# Back.net
KiCad netlist of a schematic drawn in EAGLE
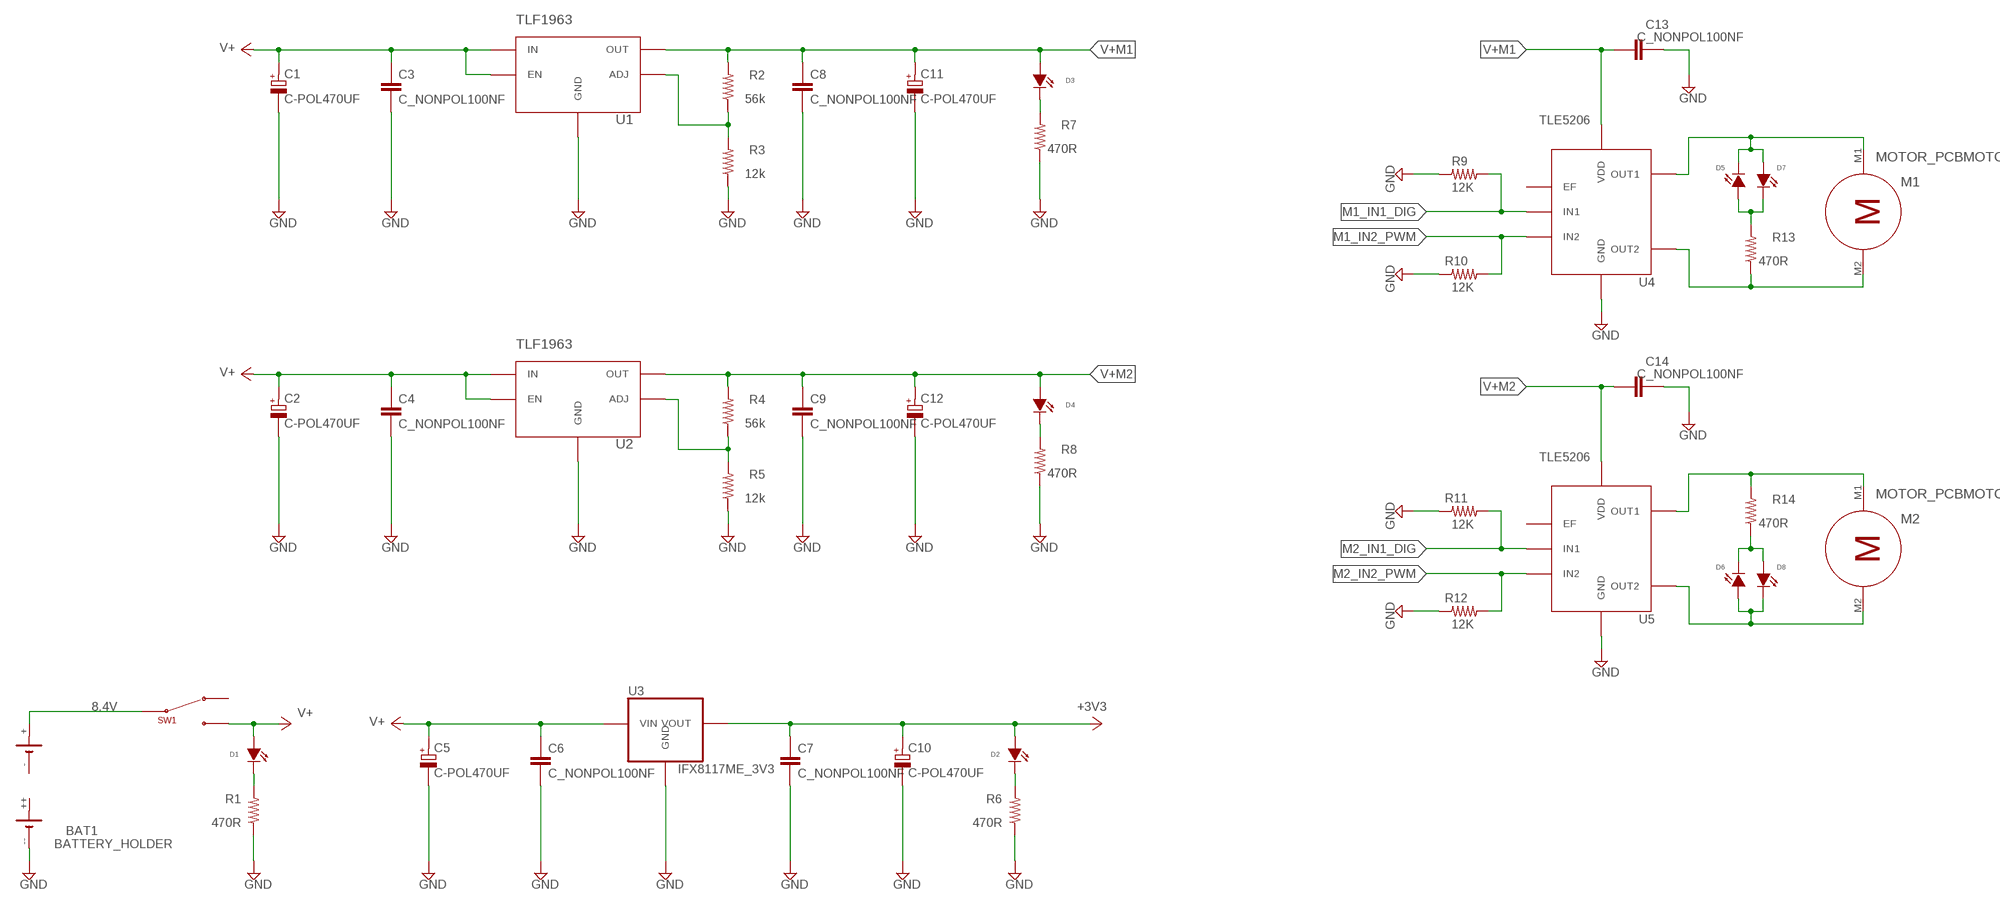
[diagram p0: schematic, sheet 1, part 1 of 2]
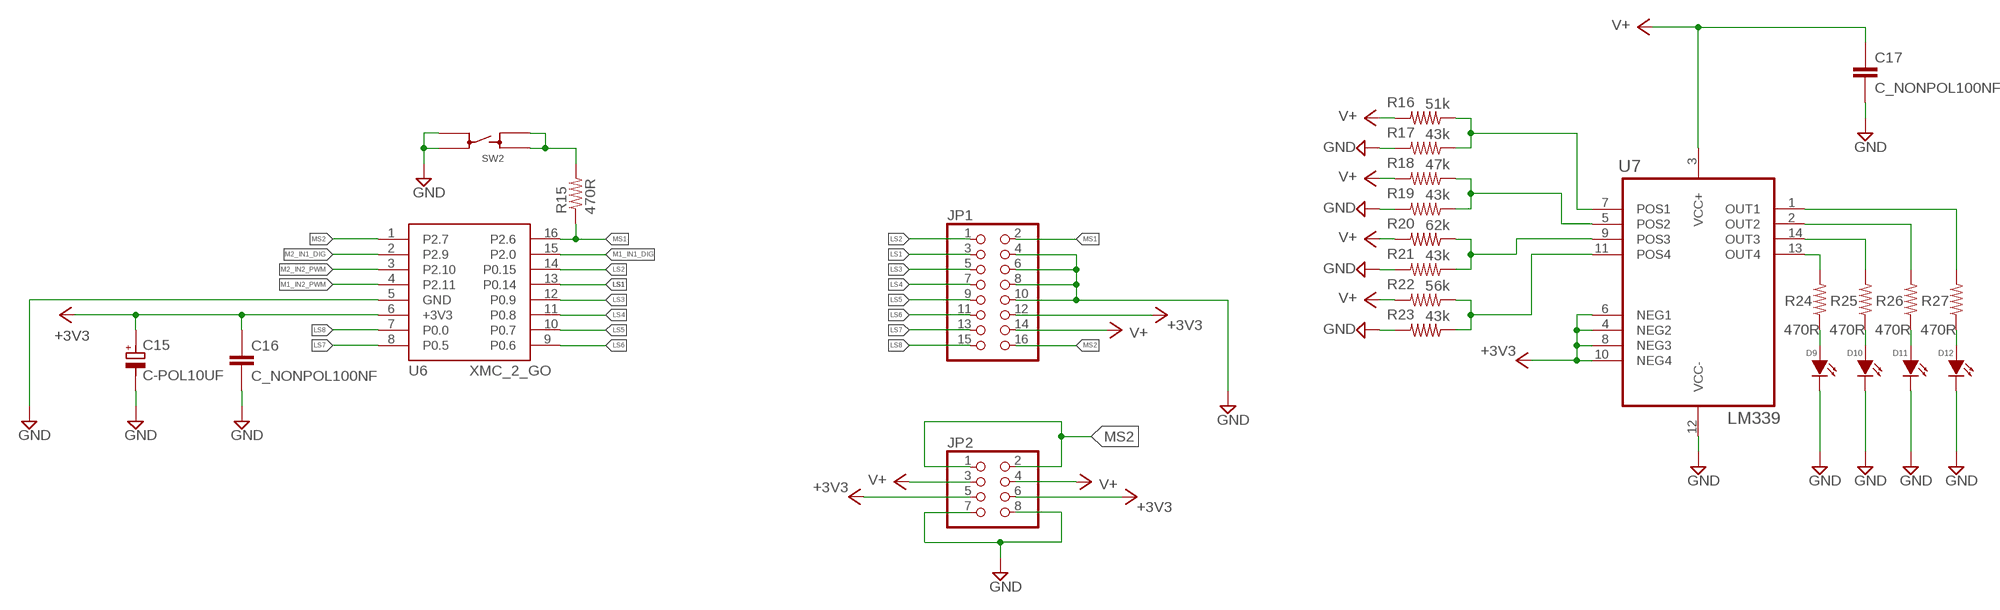
[diagram p1: schematic, sheet 1, part 2 of 2]

(export (version "E")
  (design (tool "Eeschema 10.0.6"))
  (components
    (comp (ref "BAT1")
      (value "BATTERY_HOLDER")
      (footprint "eagle-import:BATT_SUPPORT_KEYSTONE")
      (libsource (lib "eagle-import") (part "BATTERY_HOLDER"))
    )
    (comp (ref "C1")
      (value "C-POL470UF")
      (footprint "eagle-import:E3,5-8")
      (libsource (lib "eagle-import") (part "C-POL470UF"))
    )
    (comp (ref "C2")
      (value "C-POL470UF")
      (footprint "eagle-import:E3,5-8")
      (libsource (lib "eagle-import") (part "C-POL470UF"))
    )
    (comp (ref "C3")
      (value "C_NONPOL100NF")
      (footprint "eagle-import:C1206")
      (libsource (lib "eagle-import") (part "C_NONPOL100NF"))
    )
    (comp (ref "C4")
      (value "C_NONPOL100NF")
      (footprint "eagle-import:C1206")
      (libsource (lib "eagle-import") (part "C_NONPOL100NF"))
    )
    (comp (ref "C5")
      (value "C-POL470UF")
      (footprint "eagle-import:E3,5-8")
      (libsource (lib "eagle-import") (part "C-POL470UF"))
    )
    (comp (ref "C6")
      (value "C_NONPOL100NF")
      (footprint "eagle-import:C1206")
      (libsource (lib "eagle-import") (part "C_NONPOL100NF"))
    )
    (comp (ref "C7")
      (value "C_NONPOL100NF")
      (footprint "eagle-import:C1206")
      (libsource (lib "eagle-import") (part "C_NONPOL100NF"))
    )
    (comp (ref "C8")
      (value "C_NONPOL100NF")
      (footprint "eagle-import:C1206")
      (libsource (lib "eagle-import") (part "C_NONPOL100NF"))
    )
    (comp (ref "C9")
      (value "C_NONPOL100NF")
      (footprint "eagle-import:C1206")
      (libsource (lib "eagle-import") (part "C_NONPOL100NF"))
    )
    (comp (ref "C10")
      (value "C-POL470UF")
      (footprint "eagle-import:E3,5-8")
      (libsource (lib "eagle-import") (part "C-POL470UF"))
    )
    (comp (ref "C11")
      (value "C-POL470UF")
      (footprint "eagle-import:E3,5-8")
      (libsource (lib "eagle-import") (part "C-POL470UF"))
    )
    (comp (ref "C12")
      (value "C-POL470UF")
      (footprint "eagle-import:E3,5-8")
      (libsource (lib "eagle-import") (part "C-POL470UF"))
    )
    (comp (ref "C13")
      (value "C_NONPOL100NF")
      (footprint "eagle-import:C1206")
      (libsource (lib "eagle-import") (part "C_NONPOL100NF"))
    )
    (comp (ref "C14")
      (value "C_NONPOL100NF")
      (footprint "eagle-import:C1206")
      (libsource (lib "eagle-import") (part "C_NONPOL100NF"))
    )
    (comp (ref "C15")
      (value "C-POL10UF")
      (footprint "eagle-import:PANASONIC_B")
      (libsource (lib "eagle-import") (part "C-POL10UF"))
    )
    (comp (ref "C16")
      (value "C_NONPOL100NF")
      (footprint "eagle-import:C1206")
      (libsource (lib "eagle-import") (part "C_NONPOL100NF"))
    )
    (comp (ref "C17")
      (value "C_NONPOL100NF")
      (footprint "eagle-import:C1206")
      (libsource (lib "eagle-import") (part "C_NONPOL100NF"))
    )
    (comp (ref "D1")
      (value "LED")
      (footprint "eagle-import:CHIPLED_1206")
      (libsource (lib "eagle-import") (part "LED"))
    )
    (comp (ref "D2")
      (value "LED")
      (footprint "eagle-import:CHIPLED_1206")
      (libsource (lib "eagle-import") (part "LED"))
    )
    (comp (ref "D3")
      (value "LED")
      (footprint "eagle-import:CHIPLED_1206")
      (libsource (lib "eagle-import") (part "LED"))
    )
    (comp (ref "D4")
      (value "LED")
      (footprint "eagle-import:CHIPLED_1206")
      (libsource (lib "eagle-import") (part "LED"))
    )
    (comp (ref "D5")
      (value "LED")
      (footprint "eagle-import:CHIPLED_1206")
      (libsource (lib "eagle-import") (part "LED"))
    )
    (comp (ref "D6")
      (value "LED")
      (footprint "eagle-import:CHIPLED_1206")
      (libsource (lib "eagle-import") (part "LED"))
    )
    (comp (ref "D7")
      (value "LED")
      (footprint "eagle-import:CHIPLED_1206")
      (libsource (lib "eagle-import") (part "LED"))
    )
    (comp (ref "D8")
      (value "LED")
      (footprint "eagle-import:CHIPLED_1206")
      (libsource (lib "eagle-import") (part "LED"))
    )
    (comp (ref "D9")
      (value "LED")
      (footprint "eagle-import:CHIPLED_1206")
      (libsource (lib "eagle-import") (part "LED"))
    )
    (comp (ref "D10")
      (value "LED")
      (footprint "eagle-import:CHIPLED_1206")
      (libsource (lib "eagle-import") (part "LED"))
    )
    (comp (ref "D11")
      (value "LED")
      (footprint "eagle-import:CHIPLED_1206")
      (libsource (lib "eagle-import") (part "LED"))
    )
    (comp (ref "D12")
      (value "LED")
      (footprint "eagle-import:CHIPLED_1206")
      (libsource (lib "eagle-import") (part "LED"))
    )
    (comp (ref "JP1")
      (value "PINHD-2X8")
      (footprint "eagle-import:2X08")
      (libsource (lib "eagle-import") (part "PINHD-2X8"))
    )
    (comp (ref "JP2")
      (value "PINHD-2X4")
      (footprint "eagle-import:2X04")
      (libsource (lib "eagle-import") (part "PINHD-2X4"))
    )
    (comp (ref "M1")
      (value "MOTOR_PCBMOTOR")
      (footprint "eagle-import:MICRO-MOTOR")
      (libsource (lib "eagle-import") (part "MOTOR_PCBMOTOR"))
    )
    (comp (ref "M2")
      (value "MOTOR_PCBMOTOR")
      (footprint "eagle-import:MICRO-MOTOR")
      (libsource (lib "eagle-import") (part "MOTOR_PCBMOTOR"))
    )
    (comp (ref "R1")
      (value "470R")
      (footprint "eagle-import:R1206")
      (libsource (lib "eagle-import") (part "R1206"))
    )
    (comp (ref "R2")
      (value "56k")
      (footprint "eagle-import:R1206")
      (libsource (lib "eagle-import") (part "R1206"))
    )
    (comp (ref "R3")
      (value "12k")
      (footprint "eagle-import:R1206")
      (libsource (lib "eagle-import") (part "R1206"))
    )
    (comp (ref "R4")
      (value "56k")
      (footprint "eagle-import:R1206")
      (libsource (lib "eagle-import") (part "R1206"))
    )
    (comp (ref "R5")
      (value "12k")
      (footprint "eagle-import:R1206")
      (libsource (lib "eagle-import") (part "R1206"))
    )
    (comp (ref "R6")
      (value "470R")
      (footprint "eagle-import:R1206")
      (libsource (lib "eagle-import") (part "R1206"))
    )
    (comp (ref "R7")
      (value "470R")
      (footprint "eagle-import:R1206")
      (libsource (lib "eagle-import") (part "R1206"))
    )
    (comp (ref "R8")
      (value "470R")
      (footprint "eagle-import:R1206")
      (libsource (lib "eagle-import") (part "R1206"))
    )
    (comp (ref "R9")
      (value "12K")
      (footprint "eagle-import:R1206")
      (libsource (lib "eagle-import") (part "R1206"))
    )
    (comp (ref "R10")
      (value "12K")
      (footprint "eagle-import:R1206")
      (libsource (lib "eagle-import") (part "R1206"))
    )
    (comp (ref "R11")
      (value "12K")
      (footprint "eagle-import:R1206")
      (libsource (lib "eagle-import") (part "R1206"))
    )
    (comp (ref "R12")
      (value "12K")
      (footprint "eagle-import:R1206")
      (libsource (lib "eagle-import") (part "R1206"))
    )
    (comp (ref "R13")
      (value "470R")
      (footprint "eagle-import:R1206")
      (libsource (lib "eagle-import") (part "R1206"))
    )
    (comp (ref "R14")
      (value "470R")
      (footprint "eagle-import:R1206")
      (libsource (lib "eagle-import") (part "R1206"))
    )
    (comp (ref "R15")
      (value "470R")
      (footprint "eagle-import:R1206")
      (libsource (lib "eagle-import") (part "R1206"))
    )
    (comp (ref "R16")
      (value "51k")
      (footprint "eagle-import:R1206")
      (libsource (lib "eagle-import") (part "R1206"))
    )
    (comp (ref "R17")
      (value "43k")
      (footprint "eagle-import:R1206")
      (libsource (lib "eagle-import") (part "R1206"))
    )
    (comp (ref "R18")
      (value "47k")
      (footprint "eagle-import:R1206")
      (libsource (lib "eagle-import") (part "R1206"))
    )
    (comp (ref "R19")
      (value "43k")
      (footprint "eagle-import:R1206")
      (libsource (lib "eagle-import") (part "R1206"))
    )
    (comp (ref "R20")
      (value "62k")
      (footprint "eagle-import:R1206")
      (libsource (lib "eagle-import") (part "R1206"))
    )
    (comp (ref "R21")
      (value "43k")
      (footprint "eagle-import:R1206")
      (libsource (lib "eagle-import") (part "R1206"))
    )
    (comp (ref "R22")
      (value "56k")
      (footprint "eagle-import:R1206")
      (libsource (lib "eagle-import") (part "R1206"))
    )
    (comp (ref "R23")
      (value "43k")
      (footprint "eagle-import:R1206")
      (libsource (lib "eagle-import") (part "R1206"))
    )
    (comp (ref "R24")
      (value "470R")
      (footprint "eagle-import:R1206")
      (libsource (lib "eagle-import") (part "R1206"))
    )
    (comp (ref "R25")
      (value "470R")
      (footprint "eagle-import:R1206")
      (libsource (lib "eagle-import") (part "R1206"))
    )
    (comp (ref "R26")
      (value "470R")
      (footprint "eagle-import:R1206")
      (libsource (lib "eagle-import") (part "R1206"))
    )
    (comp (ref "R27")
      (value "470R")
      (footprint "eagle-import:R1206")
      (libsource (lib "eagle-import") (part "R1206"))
    )
    (comp (ref "SW1")
      (value "SWITCH1OFF2")
      (footprint "eagle-import:MS111")
      (libsource (lib "eagle-import") (part "SWITCH1OFF2"))
    )
    (comp (ref "SW2")
      (value "PUSH_BUTTON_SMD")
      (footprint "eagle-import:SWPB_SMD")
      (libsource (lib "eagle-import") (part "PUSH_BUTTON_SMD"))
    )
    (comp (ref "U1")
      (value "TLF1963")
      (footprint "eagle-import:INF-PG-TO252-5-11_L_1PRIMARY")
      (libsource (lib "eagle-import") (part "TLF1963"))
    )
    (comp (ref "U2")
      (value "TLF1963")
      (footprint "eagle-import:INF-PG-TO252-5-11_L_1PRIMARY")
      (libsource (lib "eagle-import") (part "TLF1963"))
    )
    (comp (ref "U3")
      (value "IFX8117ME_3V3")
      (footprint "eagle-import:INF-PG-SOT223_SC-73_M_1PRIMARY")
      (libsource (lib "eagle-import") (part "IFX8117ME_3V3"))
    )
    (comp (ref "U4")
      (value "TLE5206")
      (footprint "eagle-import:INF-PG-TO263-7-1_L_1PRIMARY")
      (libsource (lib "eagle-import") (part "TLE5206"))
    )
    (comp (ref "U5")
      (value "TLE5206")
      (footprint "eagle-import:INF-PG-TO263-7-1_L_1PRIMARY")
      (libsource (lib "eagle-import") (part "TLE5206"))
    )
    (comp (ref "U6")
      (value "XMC_2_GO")
      (footprint "eagle-import:XMC_2_GO")
      (libsource (lib "eagle-import") (part "XMC_2_GO"))
    )
    (comp (ref "U7")
      (value "LM339")
      (footprint "eagle-import:SO14")
      (libsource (lib "eagle-import") (part "LM339"))
    )
  )
  (nets
    (net (code "1") (name "+3V3") (class "Default")
      (node (ref "C10") (pin "+") (pinfunction "+_+") (pintype "passive"))
      (node (ref "C15") (pin "+") (pinfunction "+_+") (pintype "passive"))
      (node (ref "C16") (pin "1") (pinfunction "1_1") (pintype "passive"))
      (node (ref "C7") (pin "1") (pinfunction "1_1") (pintype "passive"))
      (node (ref "D2") (pin "A") (pinfunction "A_A") (pintype "bidirectional"))
      (node (ref "JP1") (pin "12") (pinfunction "12_12") (pintype "passive"))
      (node (ref "JP2") (pin "5") (pinfunction "5_5") (pintype "passive"))
      (node (ref "JP2") (pin "6") (pinfunction "6_6") (pintype "passive"))
      (node (ref "U3") (pin "2") (pinfunction "VOUT_2") (pintype "power_in"))
      (node (ref "U3") (pin "4") (pinfunction "VOUT_4") (pintype "power_in"))
      (node (ref "U6") (pin "6") (pinfunction "+3V3_6") (pintype "bidirectional"))
      (node (ref "U7") (pin "10") (pinfunction "NEG4_10") (pintype "input"))
      (node (ref "U7") (pin "4") (pinfunction "NEG2_4") (pintype "input"))
      (node (ref "U7") (pin "6") (pinfunction "NEG1_6") (pintype "input"))
      (node (ref "U7") (pin "8") (pinfunction "NEG3_8") (pintype "input"))
    )
    (net (code "2") (name "/8.4V") (class "Default")
      (node (ref "BAT1") (pin "+") (pinfunction "+_+") (pintype "passive"))
      (node (ref "SW1") (pin "P$2") (pinfunction "COM_P$2") (pintype "bidirectional"))
    )
    (net (code "3") (name "GND") (class "Default")
      (node (ref "BAT1") (pin "--") (pinfunction "-1_--") (pintype "passive"))
      (node (ref "C1") (pin "-") (pinfunction "-_-") (pintype "passive"))
      (node (ref "C10") (pin "-") (pinfunction "-_-") (pintype "passive"))
      (node (ref "C11") (pin "-") (pinfunction "-_-") (pintype "passive"))
      (node (ref "C12") (pin "-") (pinfunction "-_-") (pintype "passive"))
      (node (ref "C13") (pin "2") (pinfunction "2_2") (pintype "passive"))
      (node (ref "C14") (pin "2") (pinfunction "2_2") (pintype "passive"))
      (node (ref "C15") (pin "-") (pinfunction "-_-") (pintype "passive"))
      (node (ref "C16") (pin "2") (pinfunction "2_2") (pintype "passive"))
      (node (ref "C17") (pin "2") (pinfunction "2_2") (pintype "passive"))
      (node (ref "C2") (pin "-") (pinfunction "-_-") (pintype "passive"))
      (node (ref "C3") (pin "2") (pinfunction "2_2") (pintype "passive"))
      (node (ref "C4") (pin "2") (pinfunction "2_2") (pintype "passive"))
      (node (ref "C5") (pin "-") (pinfunction "-_-") (pintype "passive"))
      (node (ref "C6") (pin "2") (pinfunction "2_2") (pintype "passive"))
      (node (ref "C7") (pin "2") (pinfunction "2_2") (pintype "passive"))
      (node (ref "C8") (pin "2") (pinfunction "2_2") (pintype "passive"))
      (node (ref "C9") (pin "2") (pinfunction "2_2") (pintype "passive"))
      (node (ref "D10") (pin "C") (pinfunction "K_C") (pintype "bidirectional"))
      (node (ref "D11") (pin "C") (pinfunction "K_C") (pintype "bidirectional"))
      (node (ref "D12") (pin "C") (pinfunction "K_C") (pintype "bidirectional"))
      (node (ref "D9") (pin "C") (pinfunction "K_C") (pintype "bidirectional"))
      (node (ref "JP1") (pin "10") (pinfunction "10_10") (pintype "passive"))
      (node (ref "JP1") (pin "4") (pinfunction "4_4") (pintype "passive"))
      (node (ref "JP1") (pin "6") (pinfunction "6_6") (pintype "passive"))
      (node (ref "JP1") (pin "8") (pinfunction "8_8") (pintype "passive"))
      (node (ref "JP2") (pin "7") (pinfunction "7_7") (pintype "passive"))
      (node (ref "JP2") (pin "8") (pinfunction "8_8") (pintype "passive"))
      (node (ref "R1") (pin "1") (pinfunction "P$1_1") (pintype "passive"))
      (node (ref "R10") (pin "2") (pinfunction "P$2_2") (pintype "passive"))
      (node (ref "R11") (pin "2") (pinfunction "P$2_2") (pintype "passive"))
      (node (ref "R12") (pin "2") (pinfunction "P$2_2") (pintype "passive"))
      (node (ref "R17") (pin "2") (pinfunction "P$2_2") (pintype "passive"))
      (node (ref "R19") (pin "2") (pinfunction "P$2_2") (pintype "passive"))
      (node (ref "R21") (pin "2") (pinfunction "P$2_2") (pintype "passive"))
      (node (ref "R23") (pin "2") (pinfunction "P$2_2") (pintype "passive"))
      (node (ref "R3") (pin "1") (pinfunction "P$1_1") (pintype "passive"))
      (node (ref "R5") (pin "1") (pinfunction "P$1_1") (pintype "passive"))
      (node (ref "R6") (pin "1") (pinfunction "P$1_1") (pintype "passive"))
      (node (ref "R7") (pin "1") (pinfunction "P$1_1") (pintype "passive"))
      (node (ref "R8") (pin "1") (pinfunction "P$1_1") (pintype "passive"))
      (node (ref "R9") (pin "2") (pinfunction "P$2_2") (pintype "passive"))
      (node (ref "SW2") (pin "P$1") (pinfunction "P$1_P$1") (pintype "bidirectional"))
      (node (ref "SW2") (pin "P$2") (pinfunction "P$2_P$2") (pintype "bidirectional"))
      (node (ref "U1") (pin "3") (pinfunction "GND_3") (pintype "power_in"))
      (node (ref "U2") (pin "3") (pinfunction "GND_3") (pintype "power_in"))
      (node (ref "U3") (pin "1") (pinfunction "GND_1") (pintype "power_in"))
      (node (ref "U4") (pin "4") (pinfunction "GND_4") (pintype "power_in"))
      (node (ref "U4") (pin "8") (pinfunction "GND_8") (pintype "power_in"))
      (node (ref "U5") (pin "4") (pinfunction "GND_4") (pintype "power_in"))
      (node (ref "U5") (pin "8") (pinfunction "GND_8") (pintype "power_in"))
      (node (ref "U6") (pin "5") (pinfunction "GND_5") (pintype "bidirectional"))
      (node (ref "U7") (pin "12") (pinfunction "VCC-_12") (pintype "power_in"))
    )
    (net (code "4") (name "LS1") (class "Default")
      (node (ref "JP1") (pin "3") (pinfunction "3_3") (pintype "passive"))
      (node (ref "U6") (pin "13") (pinfunction "P0.14_13") (pintype "bidirectional"))
    )
    (net (code "5") (name "LS2") (class "Default")
      (node (ref "JP1") (pin "1") (pinfunction "1_1") (pintype "passive"))
      (node (ref "U6") (pin "14") (pinfunction "P0.15_14") (pintype "bidirectional"))
    )
    (net (code "6") (name "LS3") (class "Default")
      (node (ref "JP1") (pin "5") (pinfunction "5_5") (pintype "passive"))
      (node (ref "U6") (pin "12") (pinfunction "P0.9_12") (pintype "bidirectional"))
    )
    (net (code "7") (name "LS4") (class "Default")
      (node (ref "JP1") (pin "7") (pinfunction "7_7") (pintype "passive"))
      (node (ref "U6") (pin "11") (pinfunction "P0.8_11") (pintype "bidirectional"))
    )
    (net (code "8") (name "LS5") (class "Default")
      (node (ref "JP1") (pin "9") (pinfunction "9_9") (pintype "passive"))
      (node (ref "U6") (pin "10") (pinfunction "P0.7_10") (pintype "bidirectional"))
    )
    (net (code "9") (name "LS6") (class "Default")
      (node (ref "JP1") (pin "11") (pinfunction "11_11") (pintype "passive"))
      (node (ref "U6") (pin "9") (pinfunction "P0.6_9") (pintype "bidirectional"))
    )
    (net (code "10") (name "LS7") (class "Default")
      (node (ref "JP1") (pin "13") (pinfunction "13_13") (pintype "passive"))
      (node (ref "U6") (pin "8") (pinfunction "P0.5_8") (pintype "bidirectional"))
    )
    (net (code "11") (name "LS8") (class "Default")
      (node (ref "JP1") (pin "15") (pinfunction "15_15") (pintype "passive"))
      (node (ref "U6") (pin "7") (pinfunction "P0.0_7") (pintype "bidirectional"))
    )
    (net (code "12") (name "M1_IN1_DIG") (class "Default")
      (node (ref "R9") (pin "1") (pinfunction "P$1_1") (pintype "passive"))
      (node (ref "U4") (pin "3") (pinfunction "IN1_3") (pintype "input"))
      (node (ref "U6") (pin "15") (pinfunction "P2.0_15") (pintype "bidirectional"))
    )
    (net (code "13") (name "M1_IN2_PWM") (class "Default")
      (node (ref "R10") (pin "1") (pinfunction "P$1_1") (pintype "passive"))
      (node (ref "U4") (pin "5") (pinfunction "IN2_5") (pintype "input"))
      (node (ref "U6") (pin "4") (pinfunction "P2.11_4") (pintype "bidirectional"))
    )
    (net (code "14") (name "M2_IN1_DIG") (class "Default")
      (node (ref "R11") (pin "1") (pinfunction "P$1_1") (pintype "passive"))
      (node (ref "U5") (pin "3") (pinfunction "IN1_3") (pintype "input"))
      (node (ref "U6") (pin "2") (pinfunction "P2.9_2") (pintype "bidirectional"))
    )
    (net (code "15") (name "M2_IN2_PWM") (class "Default")
      (node (ref "R12") (pin "1") (pinfunction "P$1_1") (pintype "passive"))
      (node (ref "U5") (pin "5") (pinfunction "IN2_5") (pintype "input"))
      (node (ref "U6") (pin "3") (pinfunction "P2.10_3") (pintype "bidirectional"))
    )
    (net (code "16") (name "MS1") (class "Default")
      (node (ref "JP1") (pin "2") (pinfunction "2_2") (pintype "passive"))
      (node (ref "R15") (pin "1") (pinfunction "P$1_1") (pintype "passive"))
      (node (ref "U6") (pin "16") (pinfunction "P2.6_16") (pintype "bidirectional"))
    )
    (net (code "17") (name "MS2") (class "Default")
      (node (ref "JP1") (pin "16") (pinfunction "16_16") (pintype "passive"))
      (node (ref "JP2") (pin "1") (pinfunction "1_1") (pintype "passive"))
      (node (ref "JP2") (pin "2") (pinfunction "2_2") (pintype "passive"))
      (node (ref "U6") (pin "1") (pinfunction "P2.7_1") (pintype "bidirectional"))
    )
    (net (code "18") (name "Net-(D1-K)") (class "Default")
      (node (ref "D1") (pin "C") (pinfunction "K_C") (pintype "bidirectional"))
      (node (ref "R1") (pin "2") (pinfunction "P$2_2") (pintype "passive"))
    )
    (net (code "19") (name "Net-(D2-K)") (class "Default")
      (node (ref "D2") (pin "C") (pinfunction "K_C") (pintype "bidirectional"))
      (node (ref "R6") (pin "2") (pinfunction "P$2_2") (pintype "passive"))
    )
    (net (code "20") (name "Net-(D3-K)") (class "Default")
      (node (ref "D3") (pin "C") (pinfunction "K_C") (pintype "bidirectional"))
      (node (ref "R7") (pin "2") (pinfunction "P$2_2") (pintype "passive"))
    )
    (net (code "21") (name "Net-(D4-K)") (class "Default")
      (node (ref "D4") (pin "C") (pinfunction "K_C") (pintype "bidirectional"))
      (node (ref "R8") (pin "2") (pinfunction "P$2_2") (pintype "passive"))
    )
    (net (code "22") (name "Net-(D5-K)") (class "Default")
      (node (ref "D5") (pin "C") (pinfunction "K_C") (pintype "bidirectional"))
      (node (ref "D7") (pin "A") (pinfunction "A_A") (pintype "bidirectional"))
      (node (ref "M1") (pin "M1") (pinfunction "1_M1") (pintype "bidirectional"))
      (node (ref "U4") (pin "1") (pinfunction "OUT1_1") (pintype "output"))
    )
    (net (code "23") (name "Net-(D6-K)") (class "Default")
      (node (ref "D6") (pin "C") (pinfunction "K_C") (pintype "bidirectional"))
      (node (ref "D8") (pin "A") (pinfunction "A_A") (pintype "bidirectional"))
      (node (ref "R14") (pin "1") (pinfunction "P$1_1") (pintype "passive"))
    )
    (net (code "24") (name "Net-(D7-K)") (class "Default")
      (node (ref "D5") (pin "A") (pinfunction "A_A") (pintype "bidirectional"))
      (node (ref "D7") (pin "C") (pinfunction "K_C") (pintype "bidirectional"))
      (node (ref "R13") (pin "2") (pinfunction "P$2_2") (pintype "passive"))
    )
    (net (code "25") (name "Net-(D8-K)") (class "Default")
      (node (ref "D6") (pin "A") (pinfunction "A_A") (pintype "bidirectional"))
      (node (ref "D8") (pin "C") (pinfunction "K_C") (pintype "bidirectional"))
      (node (ref "M2") (pin "M2") (pinfunction "2_M2") (pintype "bidirectional"))
      (node (ref "U5") (pin "7") (pinfunction "OUT2_7") (pintype "output"))
    )
    (net (code "26") (name "Net-(M1-2)") (class "Default")
      (node (ref "M1") (pin "M2") (pinfunction "2_M2") (pintype "bidirectional"))
      (node (ref "R13") (pin "1") (pinfunction "P$1_1") (pintype "passive"))
      (node (ref "U4") (pin "7") (pinfunction "OUT2_7") (pintype "output"))
    )
    (net (code "27") (name "Net-(M2-1)") (class "Default")
      (node (ref "M2") (pin "M1") (pinfunction "1_M1") (pintype "bidirectional"))
      (node (ref "R14") (pin "2") (pinfunction "P$2_2") (pintype "passive"))
      (node (ref "U5") (pin "1") (pinfunction "OUT1_1") (pintype "output"))
    )
    (net (code "28") (name "Net-(R2-P$1)") (class "Default")
      (node (ref "R2") (pin "1") (pinfunction "P$1_1") (pintype "passive"))
      (node (ref "R3") (pin "2") (pinfunction "P$2_2") (pintype "passive"))
      (node (ref "U1") (pin "5") (pinfunction "ADJ_5") (pintype "bidirectional"))
    )
    (net (code "29") (name "Net-(R4-P$1)") (class "Default")
      (node (ref "R4") (pin "1") (pinfunction "P$1_1") (pintype "passive"))
      (node (ref "R5") (pin "2") (pinfunction "P$2_2") (pintype "passive"))
      (node (ref "U2") (pin "5") (pinfunction "ADJ_5") (pintype "bidirectional"))
    )
    (net (code "30") (name "Net-(R15-P$2)") (class "Default")
      (node (ref "R15") (pin "2") (pinfunction "P$2_2") (pintype "passive"))
      (node (ref "SW2") (pin "P$3") (pinfunction "P$3_P$3") (pintype "bidirectional"))
      (node (ref "SW2") (pin "P$4") (pinfunction "P$4_P$4") (pintype "bidirectional"))
    )
    (net (code "31") (name "Net-(R16-P$1)") (class "Default")
      (node (ref "R16") (pin "1") (pinfunction "P$1_1") (pintype "passive"))
      (node (ref "R17") (pin "1") (pinfunction "P$1_1") (pintype "passive"))
      (node (ref "U7") (pin "7") (pinfunction "POS1_7") (pintype "input"))
    )
    (net (code "32") (name "Net-(R18-P$1)") (class "Default")
      (node (ref "R18") (pin "1") (pinfunction "P$1_1") (pintype "passive"))
      (node (ref "R19") (pin "1") (pinfunction "P$1_1") (pintype "passive"))
      (node (ref "U7") (pin "5") (pinfunction "POS2_5") (pintype "input"))
    )
    (net (code "33") (name "Net-(R20-P$1)") (class "Default")
      (node (ref "R20") (pin "1") (pinfunction "P$1_1") (pintype "passive"))
      (node (ref "R21") (pin "1") (pinfunction "P$1_1") (pintype "passive"))
      (node (ref "U7") (pin "9") (pinfunction "POS3_9") (pintype "input"))
    )
    (net (code "34") (name "Net-(R22-P$1)") (class "Default")
      (node (ref "R22") (pin "1") (pinfunction "P$1_1") (pintype "passive"))
      (node (ref "R23") (pin "1") (pinfunction "P$1_1") (pintype "passive"))
      (node (ref "U7") (pin "11") (pinfunction "POS4_11") (pintype "input"))
    )
    (net (code "35") (name "Net-(R24-P$1)") (class "Default")
      (node (ref "D9") (pin "A") (pinfunction "A_A") (pintype "bidirectional"))
      (node (ref "R24") (pin "1") (pinfunction "P$1_1") (pintype "passive"))
    )
    (net (code "36") (name "Net-(R24-P$2)") (class "Default")
      (node (ref "R24") (pin "2") (pinfunction "P$2_2") (pintype "passive"))
      (node (ref "U7") (pin "13") (pinfunction "OUT4_13") (pintype "output"))
    )
    (net (code "37") (name "Net-(R25-P$1)") (class "Default")
      (node (ref "D10") (pin "A") (pinfunction "A_A") (pintype "bidirectional"))
      (node (ref "R25") (pin "1") (pinfunction "P$1_1") (pintype "passive"))
    )
    (net (code "38") (name "Net-(R25-P$2)") (class "Default")
      (node (ref "R25") (pin "2") (pinfunction "P$2_2") (pintype "passive"))
      (node (ref "U7") (pin "14") (pinfunction "OUT3_14") (pintype "output"))
    )
    (net (code "39") (name "Net-(R26-P$1)") (class "Default")
      (node (ref "D11") (pin "A") (pinfunction "A_A") (pintype "bidirectional"))
      (node (ref "R26") (pin "1") (pinfunction "P$1_1") (pintype "passive"))
    )
    (net (code "40") (name "Net-(R26-P$2)") (class "Default")
      (node (ref "R26") (pin "2") (pinfunction "P$2_2") (pintype "passive"))
      (node (ref "U7") (pin "2") (pinfunction "OUT2_2") (pintype "output"))
    )
    (net (code "41") (name "Net-(R27-P$1)") (class "Default")
      (node (ref "D12") (pin "A") (pinfunction "A_A") (pintype "bidirectional"))
      (node (ref "R27") (pin "1") (pinfunction "P$1_1") (pintype "passive"))
    )
    (net (code "42") (name "Net-(R27-P$2)") (class "Default")
      (node (ref "R27") (pin "2") (pinfunction "P$2_2") (pintype "passive"))
      (node (ref "U7") (pin "1") (pinfunction "OUT1_1") (pintype "output"))
    )
    (net (code "43") (name "V+") (class "Default")
      (node (ref "C1") (pin "+") (pinfunction "+_+") (pintype "passive"))
      (node (ref "C17") (pin "1") (pinfunction "1_1") (pintype "passive"))
      (node (ref "C2") (pin "+") (pinfunction "+_+") (pintype "passive"))
      (node (ref "C3") (pin "1") (pinfunction "1_1") (pintype "passive"))
      (node (ref "C4") (pin "1") (pinfunction "1_1") (pintype "passive"))
      (node (ref "C5") (pin "+") (pinfunction "+_+") (pintype "passive"))
      (node (ref "C6") (pin "1") (pinfunction "1_1") (pintype "passive"))
      (node (ref "D1") (pin "A") (pinfunction "A_A") (pintype "bidirectional"))
      (node (ref "JP1") (pin "14") (pinfunction "14_14") (pintype "passive"))
      (node (ref "JP2") (pin "3") (pinfunction "3_3") (pintype "passive"))
      (node (ref "JP2") (pin "4") (pinfunction "4_4") (pintype "passive"))
      (node (ref "R16") (pin "2") (pinfunction "P$2_2") (pintype "passive"))
      (node (ref "R18") (pin "2") (pinfunction "P$2_2") (pintype "passive"))
      (node (ref "R20") (pin "2") (pinfunction "P$2_2") (pintype "passive"))
      (node (ref "R22") (pin "2") (pinfunction "P$2_2") (pintype "passive"))
      (node (ref "SW1") (pin "P$3") (pinfunction "2_P$3") (pintype "bidirectional"))
      (node (ref "U1") (pin "1") (pinfunction "EN_1") (pintype "bidirectional"))
      (node (ref "U1") (pin "2") (pinfunction "IN_2") (pintype "power_in"))
      (node (ref "U2") (pin "1") (pinfunction "EN_1") (pintype "bidirectional"))
      (node (ref "U2") (pin "2") (pinfunction "IN_2") (pintype "power_in"))
      (node (ref "U3") (pin "3") (pinfunction "VIN_3") (pintype "power_in"))
      (node (ref "U7") (pin "3") (pinfunction "VCC+_3") (pintype "power_in"))
    )
    (net (code "44") (name "V+M1") (class "Default")
      (node (ref "C11") (pin "+") (pinfunction "+_+") (pintype "passive"))
      (node (ref "C13") (pin "1") (pinfunction "1_1") (pintype "passive"))
      (node (ref "C8") (pin "1") (pinfunction "1_1") (pintype "passive"))
      (node (ref "D3") (pin "A") (pinfunction "A_A") (pintype "bidirectional"))
      (node (ref "R2") (pin "2") (pinfunction "P$2_2") (pintype "passive"))
      (node (ref "U1") (pin "4") (pinfunction "OUT_4") (pintype "power_in"))
      (node (ref "U4") (pin "6") (pinfunction "VDD_6") (pintype "power_in"))
    )
    (net (code "45") (name "V+M2") (class "Default")
      (node (ref "C12") (pin "+") (pinfunction "+_+") (pintype "passive"))
      (node (ref "C14") (pin "1") (pinfunction "1_1") (pintype "passive"))
      (node (ref "C9") (pin "1") (pinfunction "1_1") (pintype "passive"))
      (node (ref "D4") (pin "A") (pinfunction "A_A") (pintype "bidirectional"))
      (node (ref "R4") (pin "2") (pinfunction "P$2_2") (pintype "passive"))
      (node (ref "U2") (pin "4") (pinfunction "OUT_4") (pintype "power_in"))
      (node (ref "U5") (pin "6") (pinfunction "VDD_6") (pintype "power_in"))
    )
    (net (code "46") (name "unconnected-(BAT1-+1-Pad++)") (class "Default")
      (node (ref "BAT1") (pin "++") (pinfunction "+1_++") (pintype "passive"))
    )
    (net (code "47") (name "unconnected-(BAT1-Pad-)") (class "Default")
      (node (ref "BAT1") (pin "-") (pinfunction "-_-") (pintype "passive"))
    )
    (net (code "48") (name "unconnected-(SW1-1-PadP$1)") (class "Default")
      (node (ref "SW1") (pin "P$1") (pinfunction "1_P$1") (pintype "bidirectional"))
    )
    (net (code "49") (name "unconnected-(U4-EF-Pad2)") (class "Default")
      (node (ref "U4") (pin "2") (pinfunction "EF_2") (pintype "output"))
    )
    (net (code "50") (name "unconnected-(U5-EF-Pad2)") (class "Default")
      (node (ref "U5") (pin "2") (pinfunction "EF_2") (pintype "output"))
    )
  )
)
